# Laird-BL652-v1_0_0.net
KiCad netlist of a schematic drawn in EAGLE
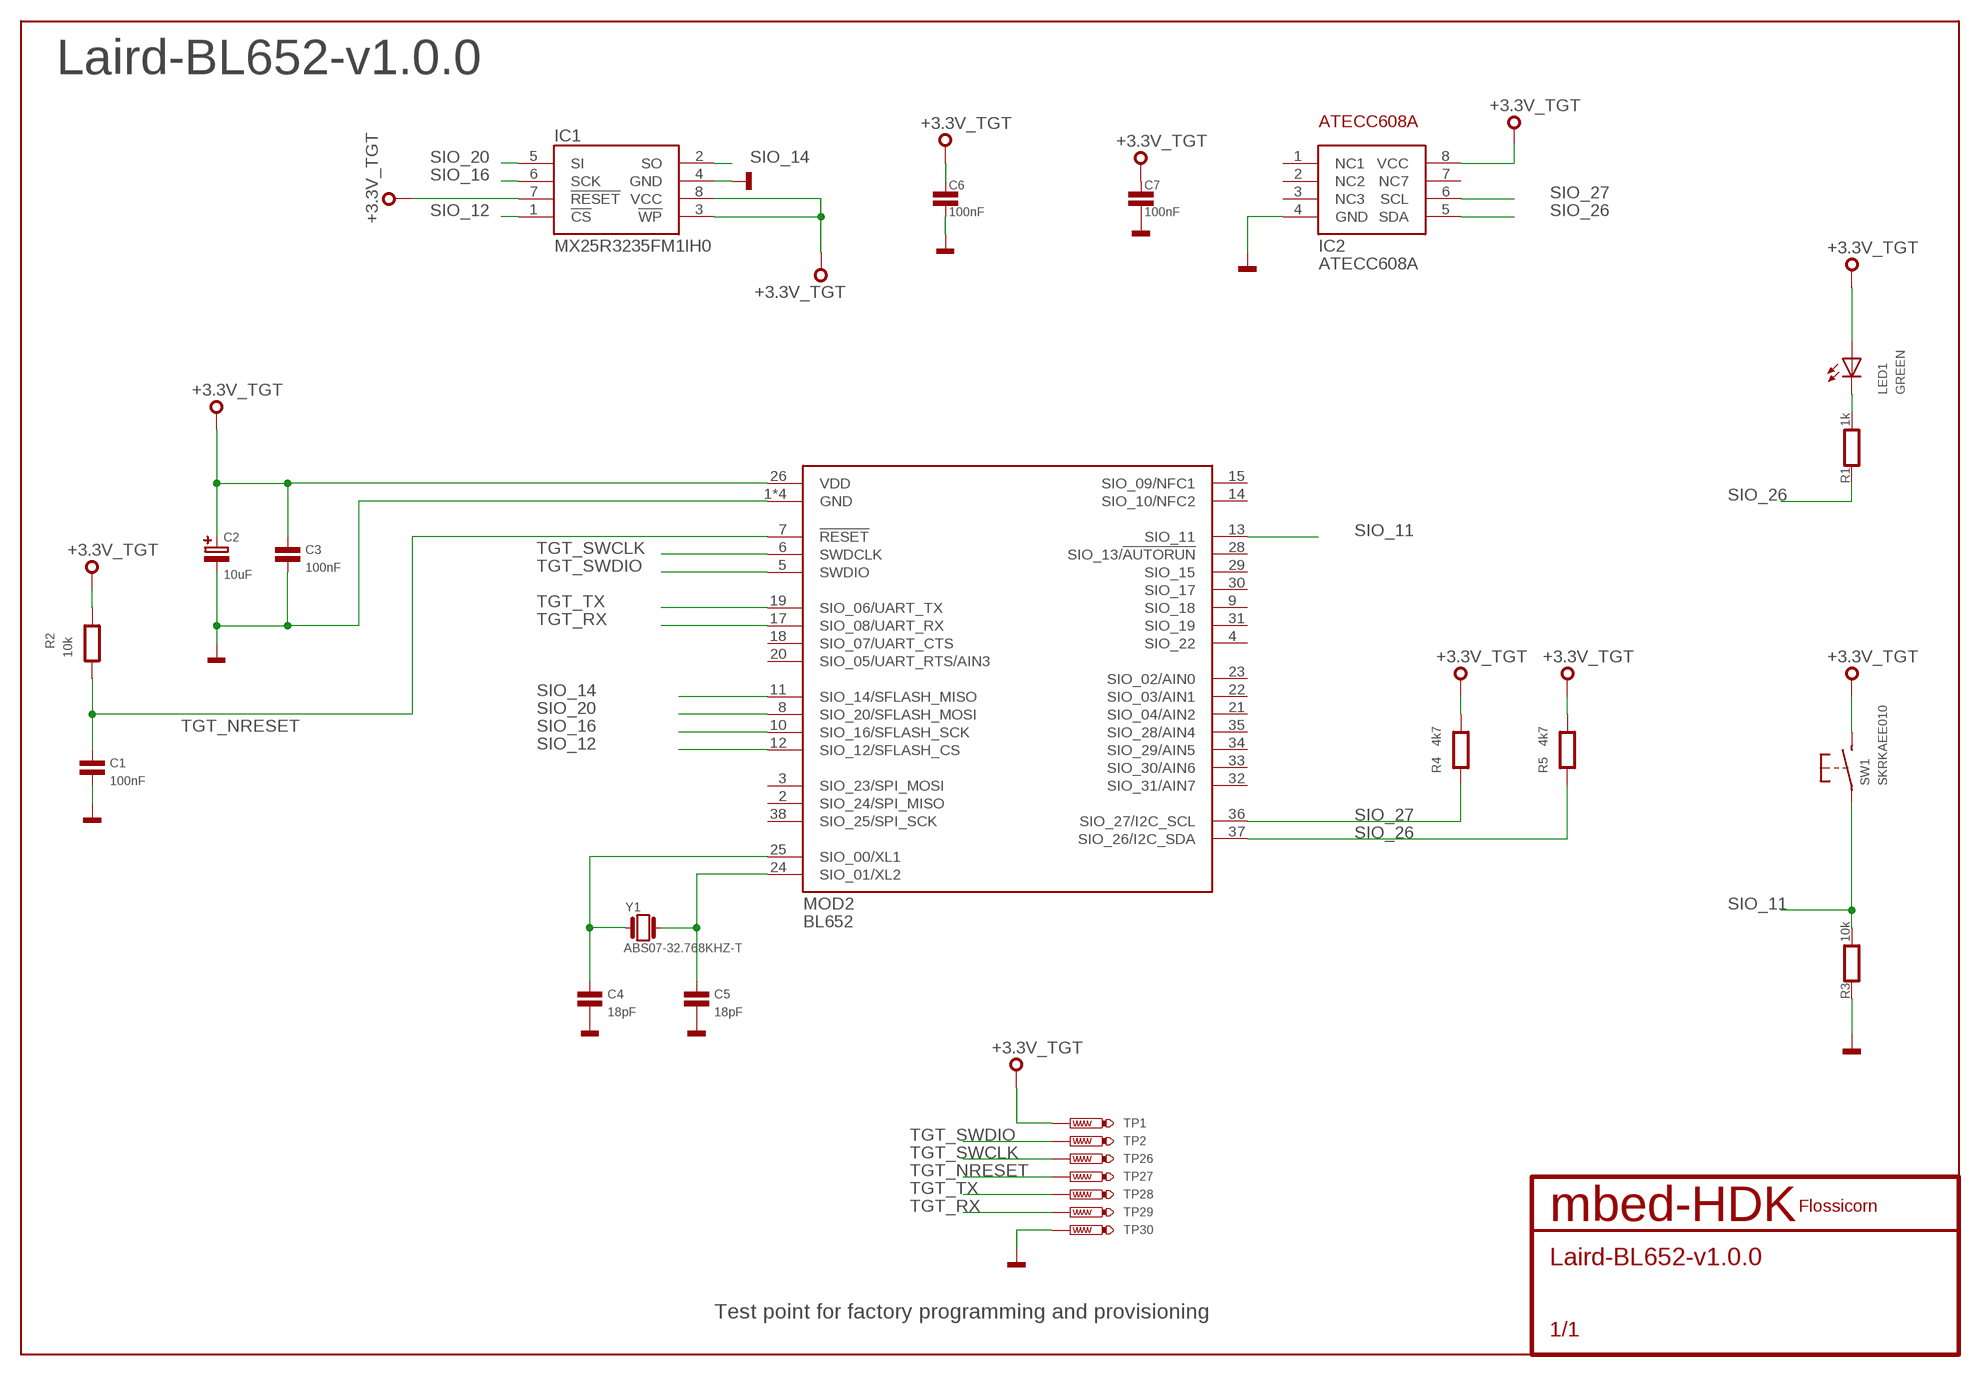
[diagram p0: schematic, sheet 1]

(export (version "E")
  (design (tool "Eeschema 10.0.6"))
  (components
    (comp (ref "C1")
      (value "100nF")
      (footprint "eagle-import:0603")
      (libsource (lib "eagle-import") (part "C0603"))
    )
    (comp (ref "C2")
      (value "10uF")
      (footprint "eagle-import:SMC_B")
      (fields (field (name "MF") "Kemet"))
      (libsource (lib "eagle-import") (part "CAPACITOR-POLARISEDB"))
    )
    (comp (ref "C3")
      (value "100nF")
      (footprint "eagle-import:0603")
      (libsource (lib "eagle-import") (part "C0603"))
    )
    (comp (ref "C4")
      (value "18pF")
      (footprint "eagle-import:0603")
      (libsource (lib "eagle-import") (part "C0603"))
    )
    (comp (ref "C5")
      (value "18pF")
      (footprint "eagle-import:0603")
      (libsource (lib "eagle-import") (part "C0603"))
    )
    (comp (ref "C6")
      (value "100nF")
      (footprint "eagle-import:0603")
      (libsource (lib "eagle-import") (part "CAPACITOR0603"))
    )
    (comp (ref "C7")
      (value "100nF")
      (footprint "eagle-import:0603")
      (libsource (lib "eagle-import") (part "CAPACITOR0603"))
    )
    (comp (ref "IC1")
      (value "MX25R3235FM1IH0")
      (footprint "eagle-import:SO8")
      (fields (field (name "MF") "Macronix"))
      (libsource (lib "eagle-import") (part "MX25R3235FM1IH0"))
    )
    (comp (ref "IC2")
      (value "ATECC608A")
      (footprint "eagle-import:SO8")
      (fields (field (name "MF") "Atmel"))
      (libsource (lib "eagle-import") (part "ATECC608A"))
    )
    (comp (ref "LED1")
      (value "GREEN")
      (footprint "eagle-import:CHIPLED_0603")
      (fields (field (name "MF") "Wurth Electronics Inc"))
      (libsource (lib "eagle-import") (part "SMD_LED0603"))
    )
    (comp (ref "MOD2")
      (value "BL652")
      (footprint "eagle-import:BL652")
      (fields (field (name "MF") "Laird"))
      (libsource (lib "eagle-import") (part "BL652"))
    )
    (comp (ref "R1")
      (value "1k")
      (footprint "eagle-import:0603")
      (libsource (lib "eagle-import") (part "RESISTOR0603"))
    )
    (comp (ref "R2")
      (value "10k")
      (footprint "eagle-import:0603")
      (libsource (lib "eagle-import") (part "RESISTOR0603"))
    )
    (comp (ref "R3")
      (value "10k")
      (footprint "eagle-import:0603")
      (libsource (lib "eagle-import") (part "RESISTOR0603"))
    )
    (comp (ref "R4")
      (value "4k7")
      (footprint "eagle-import:0603")
      (libsource (lib "eagle-import") (part "RESISTOR0603"))
    )
    (comp (ref "R5")
      (value "4k7")
      (footprint "eagle-import:0603")
      (libsource (lib "eagle-import") (part "RESISTOR0603"))
    )
    (comp (ref "SS1")
      (value "FLOSSICORN0.25")
      (footprint "eagle-import:FLOSSICORN-0.25")
      (libsource (lib "eagle-import") (part "FLOSSICORN0.25"))
    )
    (comp (ref "SW1")
      (value "SKRKAEE010")
      (footprint "eagle-import:SKRKAEE010")
      (fields (field (name "MF") "ALPS"))
      (libsource (lib "eagle-import") (part "SKRKAEE010"))
    )
    (comp (ref "TP1")
      (value "TEST_POINT-50R-SMD")
      (footprint "eagle-import:TP50-SMD")
      (libsource (lib "eagle-import") (part "TEST_POINT-50R-SMD"))
    )
    (comp (ref "TP2")
      (value "TEST_POINT-50R-SMD")
      (footprint "eagle-import:TP50-SMD")
      (libsource (lib "eagle-import") (part "TEST_POINT-50R-SMD"))
    )
    (comp (ref "TP26")
      (value "TEST_POINT-50R-SMD")
      (footprint "eagle-import:TP50-SMD")
      (libsource (lib "eagle-import") (part "TEST_POINT-50R-SMD"))
    )
    (comp (ref "TP27")
      (value "TEST_POINT-50R-SMD")
      (footprint "eagle-import:TP50-SMD")
      (libsource (lib "eagle-import") (part "TEST_POINT-50R-SMD"))
    )
    (comp (ref "TP28")
      (value "TEST_POINT-50R-SMD")
      (footprint "eagle-import:TP50-SMD")
      (libsource (lib "eagle-import") (part "TEST_POINT-50R-SMD"))
    )
    (comp (ref "TP29")
      (value "TEST_POINT-50R-SMD")
      (footprint "eagle-import:TP50-SMD")
      (libsource (lib "eagle-import") (part "TEST_POINT-50R-SMD"))
    )
    (comp (ref "TP30")
      (value "TEST_POINT-50R-SMD")
      (footprint "eagle-import:TP50-SMD")
      (libsource (lib "eagle-import") (part "TEST_POINT-50R-SMD"))
    )
    (comp (ref "Y1")
      (value "ABS07-32.768KHZ-T")
      (footprint "eagle-import:FC135")
      (fields (field (name "MF") "Abracon"))
      (libsource (lib "eagle-import") (part "ABS07-32.768KHZ-T"))
    )
  )
  (nets
    (net (code "1") (name "+3.3V_TGT") (class "Default")
      (node (ref "C2") (pin "+") (pinfunction "+_+") (pintype "passive"))
      (node (ref "C3") (pin "1") (pinfunction "P$1_1") (pintype "passive"))
      (node (ref "C6") (pin "1") (pinfunction "P$1_1") (pintype "passive"))
      (node (ref "C7") (pin "1") (pinfunction "P$1_1") (pintype "passive"))
      (node (ref "IC1") (pin "3") (pinfunction "~{WP}_3") (pintype "bidirectional"))
      (node (ref "IC1") (pin "7") (pinfunction "~{RESET}_7") (pintype "bidirectional"))
      (node (ref "IC1") (pin "8") (pinfunction "VCC_8") (pintype "bidirectional"))
      (node (ref "IC2") (pin "8") (pinfunction "VCC_8") (pintype "bidirectional"))
      (node (ref "LED1") (pin "A") (pinfunction "A_A") (pintype "passive"))
      (node (ref "MOD2") (pin "26") (pinfunction "VDD_26") (pintype "bidirectional"))
      (node (ref "R2") (pin "2") (pinfunction "P$2_2") (pintype "passive"))
      (node (ref "R4") (pin "2") (pinfunction "P$2_2") (pintype "passive"))
      (node (ref "R5") (pin "2") (pinfunction "P$2_2") (pintype "passive"))
      (node (ref "SW1") (pin "P$2") (pinfunction "S_P$2") (pintype "passive"))
      (node (ref "TP1") (pin "TP") (pinfunction "TP_TP") (pintype "input"))
    )
    (net (code "2") (name "/SIO_11") (class "Default")
      (node (ref "MOD2") (pin "13") (pinfunction "SIO_11_13") (pintype "bidirectional"))
      (node (ref "R3") (pin "2") (pinfunction "P$2_2") (pintype "passive"))
      (node (ref "SW1") (pin "P$1") (pinfunction "P_P$1") (pintype "passive"))
    )
    (net (code "3") (name "/SIO_12") (class "Default")
      (node (ref "IC1") (pin "1") (pinfunction "~{CS}_1") (pintype "bidirectional"))
      (node (ref "MOD2") (pin "12") (pinfunction "SIO_12/SFLASH_CS_12") (pintype "bidirectional"))
    )
    (net (code "4") (name "/SIO_14") (class "Default")
      (node (ref "IC1") (pin "2") (pinfunction "SO_2") (pintype "bidirectional"))
      (node (ref "MOD2") (pin "11") (pinfunction "SIO_14/SFLASH_MISO_11") (pintype "bidirectional"))
    )
    (net (code "5") (name "/SIO_16") (class "Default")
      (node (ref "IC1") (pin "6") (pinfunction "SCK_6") (pintype "bidirectional"))
      (node (ref "MOD2") (pin "10") (pinfunction "SIO_16/SFLASH_SCK_10") (pintype "bidirectional"))
    )
    (net (code "6") (name "/SIO_20") (class "Default")
      (node (ref "IC1") (pin "5") (pinfunction "SI_5") (pintype "bidirectional"))
      (node (ref "MOD2") (pin "8") (pinfunction "SIO_20/SFLASH_MOSI_8") (pintype "bidirectional"))
    )
    (net (code "7") (name "/SIO_26") (class "Default")
      (node (ref "IC2") (pin "5") (pinfunction "SDA_5") (pintype "bidirectional"))
      (node (ref "MOD2") (pin "37") (pinfunction "SIO_26/I2C_SDA_37") (pintype "bidirectional"))
      (node (ref "R1") (pin "1") (pinfunction "P$1_1") (pintype "passive"))
      (node (ref "R5") (pin "1") (pinfunction "P$1_1") (pintype "passive"))
    )
    (net (code "8") (name "/SIO_27") (class "Default")
      (node (ref "IC2") (pin "6") (pinfunction "SCL_6") (pintype "bidirectional"))
      (node (ref "MOD2") (pin "36") (pinfunction "SIO_27/I2C_SCL_36") (pintype "bidirectional"))
      (node (ref "R4") (pin "1") (pinfunction "P$1_1") (pintype "passive"))
    )
    (net (code "9") (name "/TGT_NRESET") (class "Default")
      (node (ref "C1") (pin "1") (pinfunction "P$1_1") (pintype "passive"))
      (node (ref "MOD2") (pin "7") (pinfunction "~{RESET}_7") (pintype "bidirectional"))
      (node (ref "R2") (pin "1") (pinfunction "P$1_1") (pintype "passive"))
      (node (ref "TP27") (pin "TP") (pinfunction "TP_TP") (pintype "input"))
    )
    (net (code "10") (name "/TGT_RX") (class "Default")
      (node (ref "MOD2") (pin "17") (pinfunction "SIO_08/UART_RX_17") (pintype "bidirectional"))
      (node (ref "TP29") (pin "TP") (pinfunction "TP_TP") (pintype "input"))
    )
    (net (code "11") (name "/TGT_SWCLK") (class "Default")
      (node (ref "MOD2") (pin "6") (pinfunction "SWDCLK_6") (pintype "bidirectional"))
      (node (ref "TP26") (pin "TP") (pinfunction "TP_TP") (pintype "input"))
    )
    (net (code "12") (name "/TGT_SWDIO") (class "Default")
      (node (ref "MOD2") (pin "5") (pinfunction "SWDIO_5") (pintype "bidirectional"))
      (node (ref "TP2") (pin "TP") (pinfunction "TP_TP") (pintype "input"))
    )
    (net (code "13") (name "/TGT_TX") (class "Default")
      (node (ref "MOD2") (pin "19") (pinfunction "SIO_06/UART_TX_19") (pintype "bidirectional"))
      (node (ref "TP28") (pin "TP") (pinfunction "TP_TP") (pintype "input"))
    )
    (net (code "14") (name "GND") (class "Default")
      (node (ref "C1") (pin "2") (pinfunction "P$2_2") (pintype "passive"))
      (node (ref "C2") (pin "-") (pinfunction "-_-") (pintype "passive"))
      (node (ref "C3") (pin "2") (pinfunction "P$2_2") (pintype "passive"))
      (node (ref "C4") (pin "2") (pinfunction "P$2_2") (pintype "passive"))
      (node (ref "C5") (pin "2") (pinfunction "P$2_2") (pintype "passive"))
      (node (ref "C6") (pin "2") (pinfunction "P$2_2") (pintype "passive"))
      (node (ref "C7") (pin "2") (pinfunction "P$2_2") (pintype "passive"))
      (node (ref "IC1") (pin "4") (pinfunction "GND_4") (pintype "bidirectional"))
      (node (ref "IC2") (pin "4") (pinfunction "GND_4") (pintype "bidirectional"))
      (node (ref "MOD2") (pin "1") (pinfunction "GND_1") (pintype "bidirectional"))
      (node (ref "MOD2") (pin "16") (pinfunction "GND_16") (pintype "bidirectional"))
      (node (ref "MOD2") (pin "27") (pinfunction "GND_27") (pintype "bidirectional"))
      (node (ref "MOD2") (pin "39") (pinfunction "GND_39") (pintype "bidirectional"))
      (node (ref "R3") (pin "1") (pinfunction "P$1_1") (pintype "passive"))
      (node (ref "TP30") (pin "TP") (pinfunction "TP_TP") (pintype "input"))
    )
    (net (code "15") (name "Net-(C4-P$1)") (class "Default")
      (node (ref "C4") (pin "1") (pinfunction "P$1_1") (pintype "passive"))
      (node (ref "MOD2") (pin "25") (pinfunction "SIO_00/XL1_25") (pintype "bidirectional"))
      (node (ref "Y1") (pin "X1") (pinfunction "1_X1") (pintype "passive"))
    )
    (net (code "16") (name "Net-(C5-P$1)") (class "Default")
      (node (ref "C5") (pin "1") (pinfunction "P$1_1") (pintype "passive"))
      (node (ref "MOD2") (pin "24") (pinfunction "SIO_01/XL2_24") (pintype "bidirectional"))
      (node (ref "Y1") (pin "X2") (pinfunction "2_X2") (pintype "passive"))
    )
    (net (code "17") (name "Net-(R1-P$2)") (class "Default")
      (node (ref "LED1") (pin "C") (pinfunction "C_C") (pintype "passive"))
      (node (ref "R1") (pin "2") (pinfunction "P$2_2") (pintype "passive"))
    )
    (net (code "18") (name "unconnected-(IC2-NC1-Pad1)") (class "Default")
      (node (ref "IC2") (pin "1") (pinfunction "NC1_1") (pintype "bidirectional"))
    )
    (net (code "19") (name "unconnected-(IC2-NC2-Pad2)") (class "Default")
      (node (ref "IC2") (pin "2") (pinfunction "NC2_2") (pintype "bidirectional"))
    )
    (net (code "20") (name "unconnected-(IC2-NC3-Pad3)") (class "Default")
      (node (ref "IC2") (pin "3") (pinfunction "NC3_3") (pintype "bidirectional"))
    )
    (net (code "21") (name "unconnected-(IC2-NC7-Pad7)") (class "Default")
      (node (ref "IC2") (pin "7") (pinfunction "NC7_7") (pintype "bidirectional"))
    )
    (net (code "22") (name "unconnected-(MOD2-SIO_02{slash}AIN0-Pad23)") (class "Default")
      (node (ref "MOD2") (pin "23") (pinfunction "SIO_02/AIN0_23") (pintype "bidirectional"))
    )
    (net (code "23") (name "unconnected-(MOD2-SIO_03{slash}AIN1-Pad22)") (class "Default")
      (node (ref "MOD2") (pin "22") (pinfunction "SIO_03/AIN1_22") (pintype "bidirectional"))
    )
    (net (code "24") (name "unconnected-(MOD2-SIO_04{slash}AIN2-Pad21)") (class "Default")
      (node (ref "MOD2") (pin "21") (pinfunction "SIO_04/AIN2_21") (pintype "bidirectional"))
    )
    (net (code "25") (name "unconnected-(MOD2-SIO_05{slash}UART_RTS{slash}AIN3-Pad20)") (class "Default")
      (node (ref "MOD2") (pin "20") (pinfunction "SIO_05/UART_RTS/AIN3_20") (pintype "bidirectional"))
    )
    (net (code "26") (name "unconnected-(MOD2-SIO_07{slash}UART_CTS-Pad18)") (class "Default")
      (node (ref "MOD2") (pin "18") (pinfunction "SIO_07/UART_CTS_18") (pintype "bidirectional"))
    )
    (net (code "27") (name "unconnected-(MOD2-SIO_09{slash}NFC1-Pad15)") (class "Default")
      (node (ref "MOD2") (pin "15") (pinfunction "SIO_09/NFC1_15") (pintype "bidirectional"))
    )
    (net (code "28") (name "unconnected-(MOD2-SIO_10{slash}NFC2-Pad14)") (class "Default")
      (node (ref "MOD2") (pin "14") (pinfunction "SIO_10/NFC2_14") (pintype "bidirectional"))
    )
    (net (code "29") (name "unconnected-(MOD2-SIO_13{slash}~{AUTORUN}-Pad28)") (class "Default")
      (node (ref "MOD2") (pin "28") (pinfunction "SIO_13/~{AUTORUN}_28") (pintype "bidirectional"))
    )
    (net (code "30") (name "unconnected-(MOD2-SIO_15-Pad29)") (class "Default")
      (node (ref "MOD2") (pin "29") (pinfunction "SIO_15_29") (pintype "bidirectional"))
    )
    (net (code "31") (name "unconnected-(MOD2-SIO_17-Pad30)") (class "Default")
      (node (ref "MOD2") (pin "30") (pinfunction "SIO_17_30") (pintype "bidirectional"))
    )
    (net (code "32") (name "unconnected-(MOD2-SIO_18-Pad9)") (class "Default")
      (node (ref "MOD2") (pin "9") (pinfunction "SIO_18_9") (pintype "bidirectional"))
    )
    (net (code "33") (name "unconnected-(MOD2-SIO_19-Pad31)") (class "Default")
      (node (ref "MOD2") (pin "31") (pinfunction "SIO_19_31") (pintype "bidirectional"))
    )
    (net (code "34") (name "unconnected-(MOD2-SIO_22-Pad4)") (class "Default")
      (node (ref "MOD2") (pin "4") (pinfunction "SIO_22_4") (pintype "bidirectional"))
    )
    (net (code "35") (name "unconnected-(MOD2-SIO_23{slash}SPI_MOSI-Pad3)") (class "Default")
      (node (ref "MOD2") (pin "3") (pinfunction "SIO_23/SPI_MOSI_3") (pintype "bidirectional"))
    )
    (net (code "36") (name "unconnected-(MOD2-SIO_24{slash}SPI_MISO-Pad2)") (class "Default")
      (node (ref "MOD2") (pin "2") (pinfunction "SIO_24/SPI_MISO_2") (pintype "bidirectional"))
    )
    (net (code "37") (name "unconnected-(MOD2-SIO_25{slash}SPI_SCK-Pad38)") (class "Default")
      (node (ref "MOD2") (pin "38") (pinfunction "SIO_25/SPI_SCK_38") (pintype "bidirectional"))
    )
    (net (code "38") (name "unconnected-(MOD2-SIO_28{slash}AIN4-Pad35)") (class "Default")
      (node (ref "MOD2") (pin "35") (pinfunction "SIO_28/AIN4_35") (pintype "bidirectional"))
    )
    (net (code "39") (name "unconnected-(MOD2-SIO_29{slash}AIN5-Pad34)") (class "Default")
      (node (ref "MOD2") (pin "34") (pinfunction "SIO_29/AIN5_34") (pintype "bidirectional"))
    )
    (net (code "40") (name "unconnected-(MOD2-SIO_30{slash}AIN6-Pad33)") (class "Default")
      (node (ref "MOD2") (pin "33") (pinfunction "SIO_30/AIN6_33") (pintype "bidirectional"))
    )
    (net (code "41") (name "unconnected-(MOD2-SIO_31{slash}AIN7-Pad32)") (class "Default")
      (node (ref "MOD2") (pin "32") (pinfunction "SIO_31/AIN7_32") (pintype "bidirectional"))
    )
  )
)
